# super.net
KiCad netlist of a schematic drawn in Altium Designer
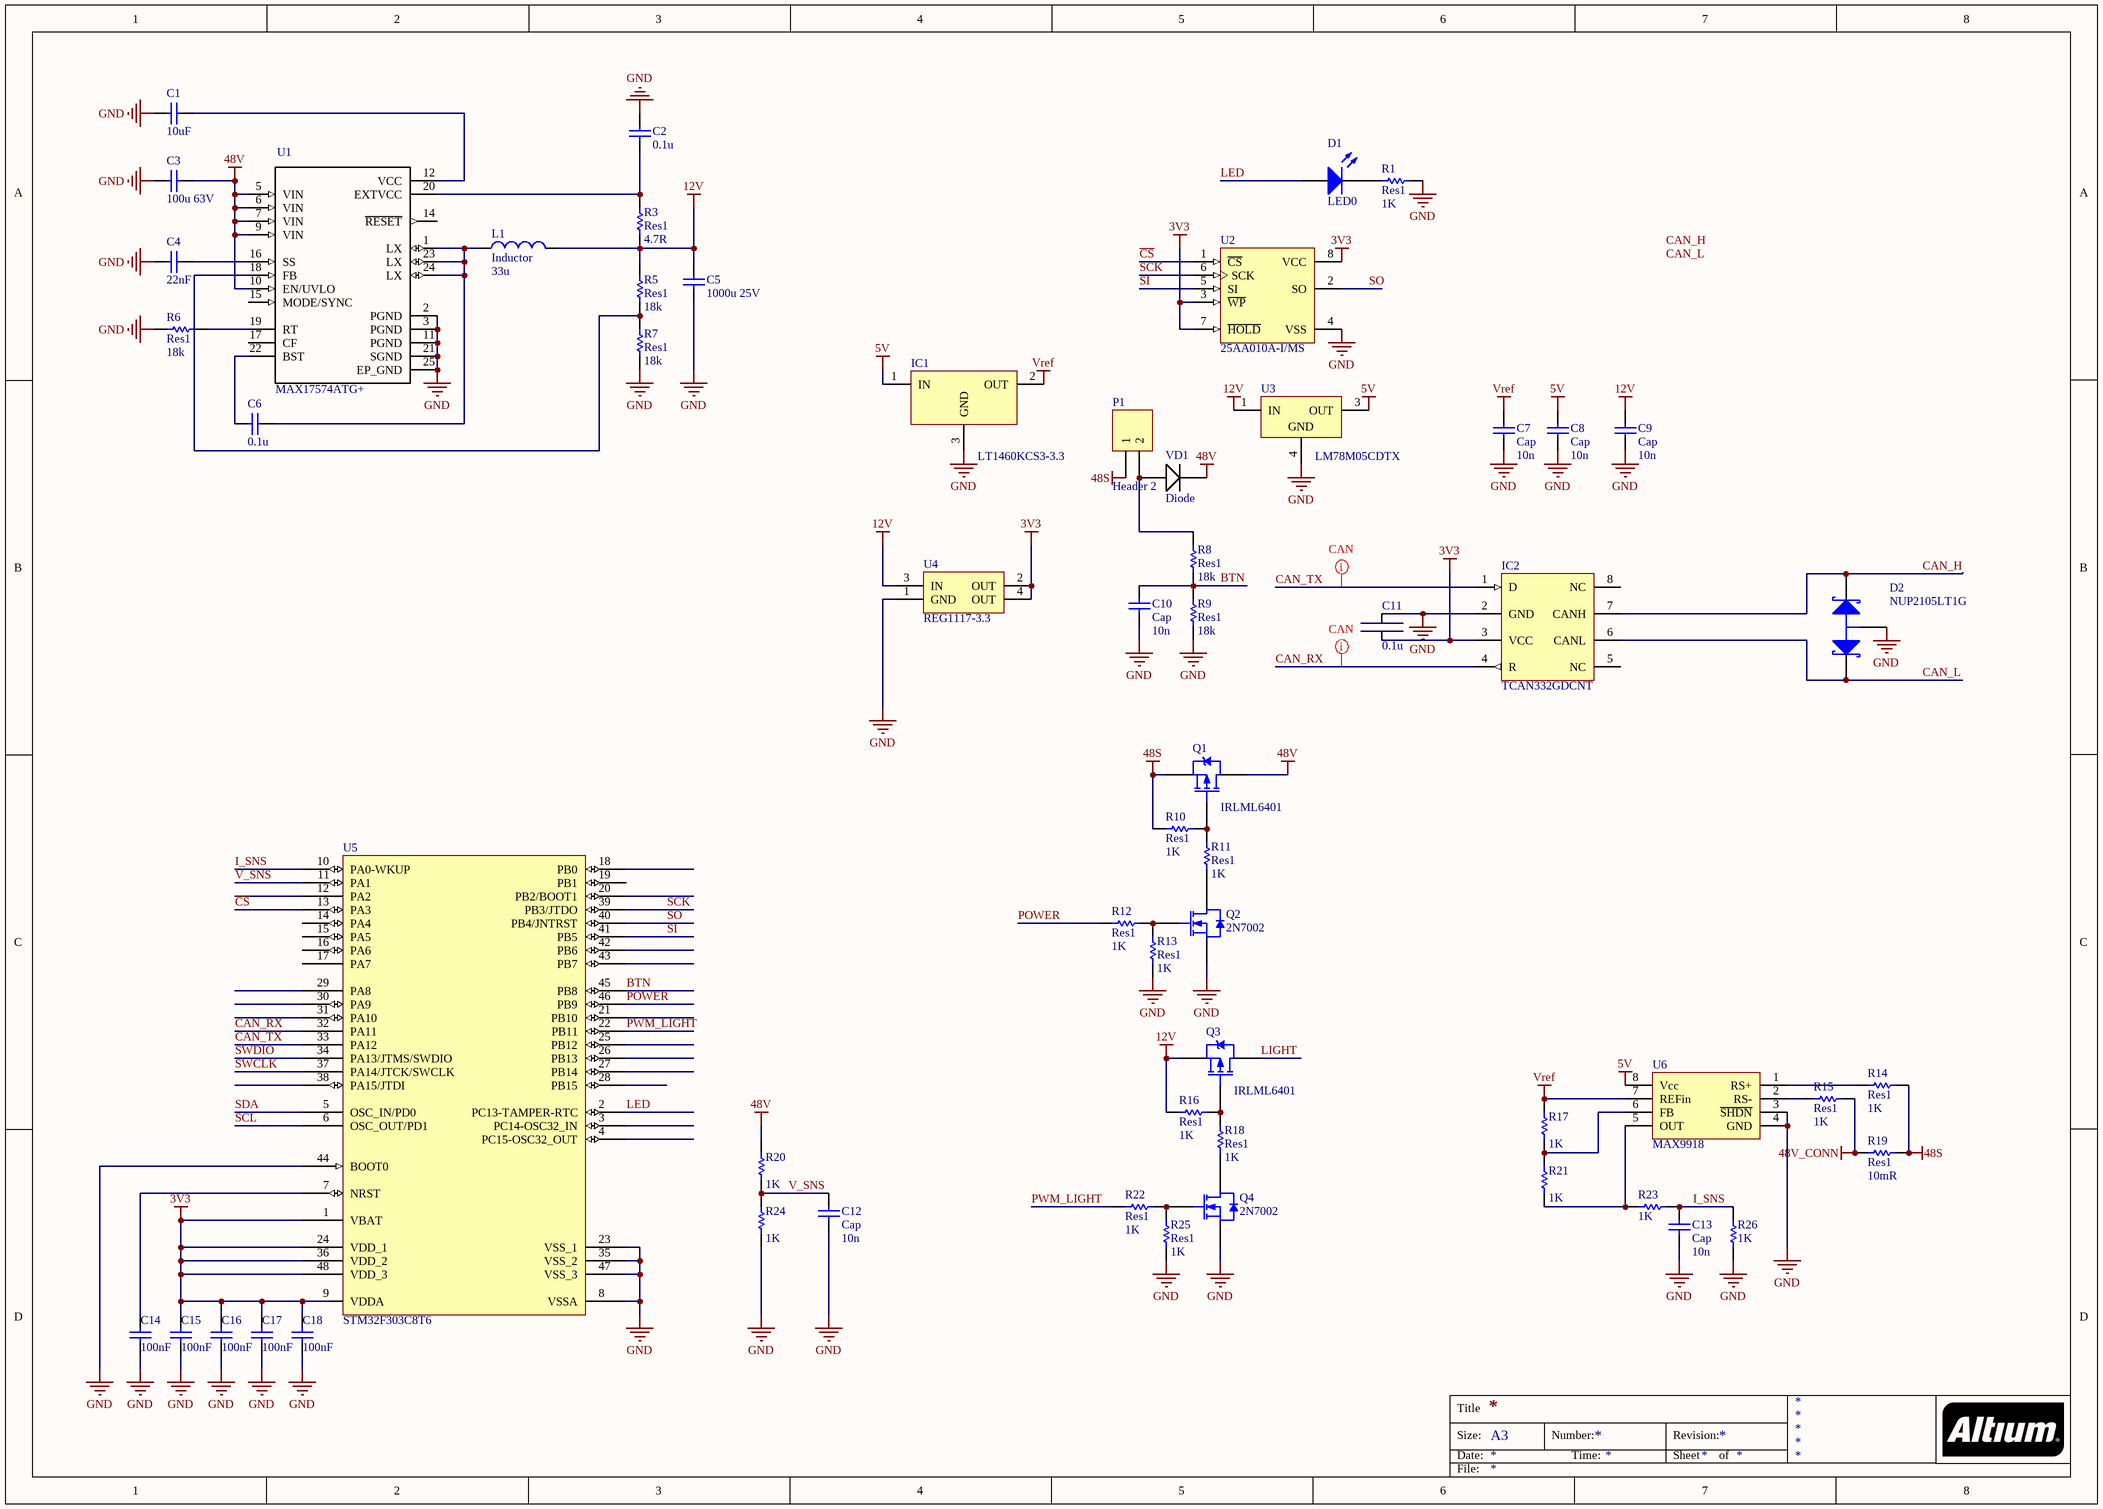
[diagram p0: super.SchDoc]

(export (version "E")
  (design (tool "Eeschema 10.0.6"))
  (components
    (comp (ref "C1")
      (value "10uF")
      (footprint "1206x")
      (description "Capacitor")
      (fields (field (name "PUBLISHER") "Altium Limited"))
      (libsource (lib "Miscellaneous Devices") (part "Cap"))
    )
    (comp (ref "C2")
      (value "0.1u")
      (footprint "0603x")
      (description "Capacitor")
      (fields (field (name "PUBLISHER") "Altium Limited"))
      (libsource (lib "Miscellaneous Devices") (part "Cap"))
    )
    (comp (ref "C3")
      (value "100u 63V")
      (footprint "CAP_ELEC_10mm")
      (description "Capacitor")
      (fields (field (name "PUBLISHER") "Altium Limited"))
      (libsource (lib "Miscellaneous Devices") (part "Cap"))
    )
    (comp (ref "C4")
      (value "22nF")
      (footprint "0603x")
      (description "Capacitor")
      (fields (field (name "PUBLISHER") "Altium Limited"))
      (libsource (lib "Miscellaneous Devices") (part "Cap"))
    )
    (comp (ref "C5")
      (value "1000u 25V")
      (footprint "CAP_ELEC_10mm")
      (description "Capacitor")
      (fields (field (name "PUBLISHER") "Altium Limited"))
      (libsource (lib "Miscellaneous Devices") (part "Cap"))
    )
    (comp (ref "C6")
      (value "0.1u")
      (footprint "0603x")
      (description "Capacitor")
      (fields (field (name "PUBLISHER") "Altium Limited"))
      (libsource (lib "Miscellaneous Devices") (part "Cap"))
    )
    (comp (ref "C7")
      (value "Cap")
      (footprint "0603x")
      (description "Capacitor")
      (fields (field (name "ALTIUM_VALUE") "10n") (field (name "PUBLISHER") "Altium Limited"))
      (libsource (lib "Miscellaneous Devices") (part "Cap"))
    )
    (comp (ref "C8")
      (value "Cap")
      (footprint "0603x")
      (description "Capacitor")
      (fields (field (name "ALTIUM_VALUE") "10n") (field (name "PUBLISHER") "Altium Limited"))
      (libsource (lib "Miscellaneous Devices") (part "Cap"))
    )
    (comp (ref "C9")
      (value "Cap")
      (footprint "0603x")
      (description "Capacitor")
      (fields (field (name "ALTIUM_VALUE") "10n") (field (name "PUBLISHER") "Altium Limited"))
      (libsource (lib "Miscellaneous Devices") (part "Cap"))
    )
    (comp (ref "C10")
      (value "Cap")
      (footprint "0603x")
      (description "Capacitor")
      (fields (field (name "ALTIUM_VALUE") "10n") (field (name "PUBLISHER") "Altium Limited"))
      (libsource (lib "Miscellaneous Devices") (part "Cap"))
    )
    (comp (ref "C11")
      (value "0.1u")
      (footprint "Condensator:CAPC1608X08N(0603)")
      (libsource (lib "Condensator") (part "Ceramic Chip Capacitor"))
    )
    (comp (ref "C12")
      (value "Cap")
      (footprint "0603x")
      (description "Capacitor")
      (fields (field (name "ALTIUM_VALUE") "10n") (field (name "PUBLISHER") "Altium Limited"))
      (libsource (lib "Miscellaneous Devices") (part "Cap"))
    )
    (comp (ref "C13")
      (value "Cap")
      (footprint "0603x")
      (description "Capacitor")
      (fields (field (name "ALTIUM_VALUE") "10n") (field (name "PUBLISHER") "Altium Limited"))
      (libsource (lib "Miscellaneous Devices") (part "Cap"))
    )
    (comp (ref "C14")
      (value "100nF")
      (footprint "0603x")
      (description "Capacitor")
      (fields (field (name "Comment") "Cap") (field (name "PUBLISHER") "Altium Limited"))
      (libsource (lib "Miscellaneous Devices") (part "Cap"))
    )
    (comp (ref "C15")
      (value "100nF")
      (footprint "0603x")
      (description "Capacitor")
      (fields (field (name "Comment") "Cap") (field (name "PUBLISHER") "Altium Limited"))
      (libsource (lib "Miscellaneous Devices") (part "Cap"))
    )
    (comp (ref "C16")
      (value "100nF")
      (footprint "0603x")
      (description "Capacitor")
      (fields (field (name "Comment") "Cap") (field (name "PUBLISHER") "Altium Limited"))
      (libsource (lib "Miscellaneous Devices") (part "Cap"))
    )
    (comp (ref "C17")
      (value "100nF")
      (footprint "0603x")
      (description "Capacitor")
      (fields (field (name "Comment") "Cap") (field (name "PUBLISHER") "Altium Limited"))
      (libsource (lib "Miscellaneous Devices") (part "Cap"))
    )
    (comp (ref "C18")
      (value "100nF")
      (footprint "0603x")
      (description "Capacitor")
      (fields (field (name "Comment") "Cap") (field (name "PUBLISHER") "Altium Limited"))
      (libsource (lib "Miscellaneous Devices") (part "Cap"))
    )
    (comp (ref "D1")
      (value "LED0")
      (footprint "HDR1X2")
      (description "Typical INFRARED GaAs LED")
      (fields (field (name "PUBLISHER") "Altium Limited"))
      (libsource (lib "Miscellaneous Devices") (part "LED0"))
    )
    (comp (ref "D2")
      (value "NUP2105LT1G")
      (footprint "SOT-23_M")
      (description "Schottky Barrier Double Diode")
      (libsource (lib "Philips Discrete Diode - Schottky") (part "BAT54A"))
    )
    (comp (ref "IC1")
      (value "LT1460KCS3-3.3")
      (footprint "SOT23_N")
      (libsource (lib "CustomLib") (part "PreciseRef"))
    )
    (comp (ref "IC2")
      (value "TCAN332GDCNT")
      (footprint "SOT23-8_L")
      (libsource (lib "CustomLib") (part "TCAN332GDCNT"))
    )
    (comp (ref "L1")
      (value "Inductor")
      (footprint "DR74")
      (fields (field (name "ALTIUM_VALUE") "33u") (field (name "PUBLISHER") "Altium Limited"))
      (libsource (lib "Miscellaneous Devices") (part "Inductor"))
    )
    (comp (ref "P1")
      (value "Header 2")
      (footprint "HDR1X2")
      (description "Header, 2-Pin")
      (fields (field (name "PUBLISHER") "Altium Limited"))
      (libsource (lib "Miscellaneous Connectors") (part "Header 2"))
    )
    (comp (ref "Q1")
      (value "IRLML6401")
      (footprint "Micro3_N")
      (description "HEXFET Power MOSFET")
      (fields (field (name "PUBLISHER") "Altium Limited"))
      (libsource (lib "IR Discrete MOSFET - Power") (part "IRLML6401"))
    )
    (comp (ref "Q2")
      (value "2N7002")
      (footprint "SOT23_N")
      (description "N-channel Enhancement Mode Field-effect Transistor")
      (fields (field (name "PUBLISHER") "Altium Limited"))
      (libsource (lib "Philips Discrete MOSFET - Low Power") (part "2N7002"))
    )
    (comp (ref "Q3")
      (value "IRLML6401")
      (footprint "Micro3_N")
      (description "HEXFET Power MOSFET")
      (fields (field (name "PUBLISHER") "Altium Limited"))
      (libsource (lib "IR Discrete MOSFET - Power") (part "IRLML6401"))
    )
    (comp (ref "Q4")
      (value "2N7002")
      (footprint "SOT23_N")
      (description "N-channel Enhancement Mode Field-effect Transistor")
      (fields (field (name "PUBLISHER") "Altium Limited"))
      (libsource (lib "Philips Discrete MOSFET - Low Power") (part "2N7002"))
    )
    (comp (ref "R1")
      (value "Res1")
      (footprint "0603x")
      (description "Resistor")
      (fields (field (name "ALTIUM_VALUE") "1K") (field (name "PUBLISHER") "Altium Limited"))
      (libsource (lib "Miscellaneous Devices") (part "Res1"))
    )
    (comp (ref "R3")
      (value "Res1")
      (footprint "0603x")
      (description "Resistor")
      (fields (field (name "ALTIUM_VALUE") "4.7R") (field (name "PUBLISHER") "Altium Limited"))
      (libsource (lib "Miscellaneous Devices") (part "Res1"))
    )
    (comp (ref "R5")
      (value "Res1")
      (footprint "0603x")
      (description "Resistor")
      (fields (field (name "ALTIUM_VALUE") "18k") (field (name "PUBLISHER") "Altium Limited"))
      (libsource (lib "Miscellaneous Devices") (part "Res1"))
    )
    (comp (ref "R6")
      (value "Res1")
      (footprint "0603x")
      (description "Resistor")
      (fields (field (name "ALTIUM_VALUE") "18k") (field (name "PUBLISHER") "Altium Limited"))
      (libsource (lib "Miscellaneous Devices") (part "Res1"))
    )
    (comp (ref "R7")
      (value "Res1")
      (footprint "0603x")
      (description "Resistor")
      (fields (field (name "ALTIUM_VALUE") "18k") (field (name "PUBLISHER") "Altium Limited"))
      (libsource (lib "Miscellaneous Devices") (part "Res1"))
    )
    (comp (ref "R8")
      (value "Res1")
      (footprint "0603x")
      (description "Resistor")
      (fields (field (name "ALTIUM_VALUE") "18k") (field (name "PUBLISHER") "Altium Limited"))
      (libsource (lib "Miscellaneous Devices") (part "Res1"))
    )
    (comp (ref "R9")
      (value "Res1")
      (footprint "0603x")
      (description "Resistor")
      (fields (field (name "ALTIUM_VALUE") "18k") (field (name "PUBLISHER") "Altium Limited"))
      (libsource (lib "Miscellaneous Devices") (part "Res1"))
    )
    (comp (ref "R10")
      (value "Res1")
      (footprint "0603x")
      (description "Resistor")
      (fields (field (name "ALTIUM_VALUE") "1K") (field (name "PUBLISHER") "Altium Limited"))
      (libsource (lib "Miscellaneous Devices") (part "Res1"))
    )
    (comp (ref "R11")
      (value "Res1")
      (footprint "0603x")
      (description "Resistor")
      (fields (field (name "ALTIUM_VALUE") "1K") (field (name "PUBLISHER") "Altium Limited"))
      (libsource (lib "Miscellaneous Devices") (part "Res1"))
    )
    (comp (ref "R12")
      (value "Res1")
      (footprint "1206x")
      (description "Resistor")
      (fields (field (name "ALTIUM_VALUE") "1K") (field (name "PUBLISHER") "Altium Limited"))
      (libsource (lib "Miscellaneous Devices") (part "Res1"))
    )
    (comp (ref "R13")
      (value "Res1")
      (footprint "0603x")
      (description "Resistor")
      (fields (field (name "ALTIUM_VALUE") "1K") (field (name "PUBLISHER") "Altium Limited"))
      (libsource (lib "Miscellaneous Devices") (part "Res1"))
    )
    (comp (ref "R14")
      (value "Res1")
      (footprint "0603x")
      (description "Resistor")
      (fields (field (name "ALTIUM_VALUE") "1K") (field (name "PUBLISHER") "Altium Limited"))
      (libsource (lib "Miscellaneous Devices") (part "Res1"))
    )
    (comp (ref "R15")
      (value "Res1")
      (footprint "0603x")
      (description "Resistor")
      (fields (field (name "ALTIUM_VALUE") "1K") (field (name "PUBLISHER") "Altium Limited"))
      (libsource (lib "Miscellaneous Devices") (part "Res1"))
    )
    (comp (ref "R16")
      (value "Res1")
      (footprint "0603x")
      (description "Resistor")
      (fields (field (name "ALTIUM_VALUE") "1K") (field (name "PUBLISHER") "Altium Limited"))
      (libsource (lib "Miscellaneous Devices") (part "Res1"))
    )
    (comp (ref "R17")
      (value "1K")
      (footprint "0603x")
      (description "Resistor")
      (fields (field (name "Comment") "Res1") (field (name "PUBLISHER") "Altium Limited"))
      (libsource (lib "Miscellaneous Devices") (part "Res1"))
    )
    (comp (ref "R18")
      (value "Res1")
      (footprint "0603x")
      (description "Resistor")
      (fields (field (name "ALTIUM_VALUE") "1K") (field (name "PUBLISHER") "Altium Limited"))
      (libsource (lib "Miscellaneous Devices") (part "Res1"))
    )
    (comp (ref "R19")
      (value "Res1")
      (footprint "2512")
      (description "Resistor")
      (fields (field (name "ALTIUM_VALUE") "10mR") (field (name "PUBLISHER") "Altium Limited"))
      (libsource (lib "Miscellaneous Devices") (part "Res1"))
    )
    (comp (ref "R20")
      (value "1K")
      (footprint "0603x")
      (description "Resistor")
      (fields (field (name "Comment") "Res1") (field (name "PUBLISHER") "Altium Limited"))
      (libsource (lib "Miscellaneous Devices") (part "Res1"))
    )
    (comp (ref "R21")
      (value "1K")
      (footprint "0603x")
      (description "Resistor")
      (fields (field (name "Comment") "Res1") (field (name "PUBLISHER") "Altium Limited"))
      (libsource (lib "Miscellaneous Devices") (part "Res1"))
    )
    (comp (ref "R22")
      (value "Res1")
      (footprint "0603x")
      (description "Resistor")
      (fields (field (name "ALTIUM_VALUE") "1K") (field (name "PUBLISHER") "Altium Limited"))
      (libsource (lib "Miscellaneous Devices") (part "Res1"))
    )
    (comp (ref "R23")
      (value "1K")
      (footprint "1206x")
      (description "Resistor")
      (fields (field (name "Comment") "Res1") (field (name "PUBLISHER") "Altium Limited"))
      (libsource (lib "Miscellaneous Devices") (part "Res1"))
    )
    (comp (ref "R24")
      (value "1K")
      (footprint "0603x")
      (description "Resistor")
      (fields (field (name "Comment") "Res1") (field (name "PUBLISHER") "Altium Limited"))
      (libsource (lib "Miscellaneous Devices") (part "Res1"))
    )
    (comp (ref "R25")
      (value "Res1")
      (footprint "0603x")
      (description "Resistor")
      (fields (field (name "ALTIUM_VALUE") "1K") (field (name "PUBLISHER") "Altium Limited"))
      (libsource (lib "Miscellaneous Devices") (part "Res1"))
    )
    (comp (ref "R26")
      (value "1K")
      (footprint "0603x")
      (description "Resistor")
      (fields (field (name "Comment") "Res1") (field (name "PUBLISHER") "Altium Limited"))
      (libsource (lib "Miscellaneous Devices") (part "Res1"))
    )
    (comp (ref "U1")
      (value "MAX17574ATG+")
      (footprint "QFN50P500X400X80-25N")
      (description "IC REG BUCK ADJ 3A SYNC 24TQFN")
      (fields (field (name "DIGI-KEY_PART_NUMBER") "MAX17574ATG+-ND") (field (name "MF") "Maxim Integrated"))
      (libsource (lib "MAX17574ATG_") (part "MAX17574ATG+"))
    )
    (comp (ref "U2")
      (value "25AA010A-I/MS")
      (footprint "SO-8_N")
      (description "1K SPI Bus Serial EEPROM, 8-Pin MSOP, Industrial Temperature")
      (fields (field (name "PUBLISHER") "Altium Limited"))
      (libsource (lib "Microchip Memory SPI Serial EEPROM") (part "25AA010A-I/MS"))
    )
    (comp (ref "U3")
      (value "LM78M05CDTX")
      (footprint "TO-252AA_L")
      (description "3-Terminal Positive Voltage Regulators, 3-pin TO-252")
      (fields
        (field (name "MANUFACTURER") "National Semiconductor")
        (field (name "PUBLISHER") "Altium Limited")
      )
      (libsource (lib "NSC LDO") (part "LM78M05CDTX"))
    )
    (comp (ref "U4")
      (value "REG1117-3.3")
      (footprint "SOt-223_L")
      (description "800mA and 1A Low Dropout Positive Regulator 2.85V, 3.3V, 5V, and Adjustable")
      (fields (field (name "PUBLISHER") "Altium Limited"))
      (libsource (lib "BB Power Mgt Voltage Regulator") (part "REG1117-3.3"))
    )
    (comp (ref "U5")
      (value "STM32F303C8T6")
      (footprint "LQFP48_N")
      (description "STM32 ARM-based 32-bit MCU with 32 Kbytes Flash, 48-pin LQFP, Industrial Temperature")
      (fields (field (name "PUBLISHER") "Altium Limited"))
      (libsource (lib "ST Microcontroller 32-Bit STM32") (part "STM32F103C6T6"))
    )
    (comp (ref "U6") (value "MAX9918") (footprint "SO8_M") (libsource (lib "CustomLib") (part "MAX9918")))
    (comp (ref "VD1")
      (value "Diode")
      (footprint "SOD-80/MLL34")
      (description "Default Diode")
      (fields (field (name "PUBLISHER") "Altium Limited"))
      (libsource (lib "EDDLib") (part "Diode"))
    )
  )
  (nets
    (net (code "1") (name "/BTN") (class "Default")
      (node (ref "C10") (pin "1") (pinfunction "1_1") (pintype "passive"))
      (node (ref "R8") (pin "1") (pinfunction "1_1") (pintype "passive"))
      (node (ref "R9") (pin "2") (pinfunction "2_2") (pintype "passive"))
      (node (ref "U5") (pin "45") (pinfunction "PB8_45") (pintype "bidirectional"))
    )
    (net (code "2") (name "/CAN_H") (class "Default")
      (node (ref "D2") (pin "2") (pinfunction "K2_2") (pintype "passive"))
      (node (ref "IC2") (pin "7") (pinfunction "CANH_7") (pintype "passive"))
    )
    (net (code "3") (name "/CAN_L") (class "Default")
      (node (ref "D2") (pin "1") (pinfunction "K1_1") (pintype "passive"))
      (node (ref "IC2") (pin "6") (pinfunction "CANL_6") (pintype "passive"))
    )
    (net (code "4") (name "/CAN_RX") (class "Default")
      (node (ref "IC2") (pin "4") (pinfunction "R_4") (pintype "output"))
      (node (ref "U5") (pin "32") (pinfunction "PA11_32") (pintype "passive"))
    )
    (net (code "5") (name "/CAN_TX") (class "Default")
      (node (ref "IC2") (pin "1") (pinfunction "D_1") (pintype "input"))
      (node (ref "U5") (pin "33") (pinfunction "PA12_33") (pintype "passive"))
    )
    (net (code "6") (name "/I_SNS") (class "Default")
      (node (ref "C13") (pin "1") (pinfunction "1_1") (pintype "passive"))
      (node (ref "R23") (pin "2") (pinfunction "2_2") (pintype "passive"))
      (node (ref "R26") (pin "2") (pinfunction "2_2") (pintype "passive"))
      (node (ref "U5") (pin "10") (pinfunction "PA0-WKUP_10") (pintype "bidirectional"))
    )
    (net (code "7") (name "/LED") (class "Default")
      (node (ref "D1") (pin "1") (pinfunction "A_1") (pintype "passive"))
      (node (ref "U5") (pin "2") (pinfunction "PC13-TAMPER-RTC_2") (pintype "bidirectional"))
    )
    (net (code "8") (name "/LIGHT") (class "Default")
      (node (ref "Q3") (pin "3") (pinfunction "D_3") (pintype "passive"))
    )
    (net (code "9") (name "/POWER") (class "Default")
      (node (ref "R12") (pin "1") (pinfunction "1_1") (pintype "passive"))
      (node (ref "U5") (pin "46") (pinfunction "PB9_46") (pintype "bidirectional"))
    )
    (net (code "10") (name "/PWM_LIGHT") (class "Default")
      (node (ref "R22") (pin "1") (pinfunction "1_1") (pintype "passive"))
      (node (ref "U5") (pin "22") (pinfunction "PB11_22") (pintype "bidirectional"))
    )
    (net (code "11") (name "/SCK") (class "Default")
      (node (ref "U2") (pin "6") (pinfunction "SCK_6") (pintype "input"))
      (node (ref "U5") (pin "39") (pinfunction "PB3/JTDO_39") (pintype "bidirectional"))
    )
    (net (code "12") (name "/SCL") (class "Default")
      (node (ref "U5") (pin "6") (pinfunction "OSC_OUT/PD1_6") (pintype "passive"))
    )
    (net (code "13") (name "/SDA") (class "Default")
      (node (ref "U5") (pin "5") (pinfunction "OSC_IN/PD0_5") (pintype "passive"))
    )
    (net (code "14") (name "/SI") (class "Default")
      (node (ref "U2") (pin "5") (pinfunction "SI_5") (pintype "input"))
      (node (ref "U5") (pin "41") (pinfunction "PB5_41") (pintype "bidirectional"))
    )
    (net (code "15") (name "/SO") (class "Default")
      (node (ref "U2") (pin "2") (pinfunction "SO_2") (pintype "tri_state"))
      (node (ref "U5") (pin "40") (pinfunction "PB4/JNTRST_40") (pintype "bidirectional"))
    )
    (net (code "16") (name "/SWCLK") (class "Default")
      (node (ref "U5") (pin "37") (pinfunction "PA14/JTCK/SWCLK_37") (pintype "passive"))
    )
    (net (code "17") (name "/SWDIO") (class "Default")
      (node (ref "U5") (pin "34") (pinfunction "PA13/JTMS/SWDIO_34") (pintype "passive"))
    )
    (net (code "18") (name "/V_SNS") (class "Default")
      (node (ref "C12") (pin "1") (pinfunction "1_1") (pintype "passive"))
      (node (ref "R20") (pin "2") (pinfunction "2_2") (pintype "passive"))
      (node (ref "R24") (pin "1") (pinfunction "1_1") (pintype "passive"))
      (node (ref "U5") (pin "11") (pinfunction "PA1_11") (pintype "bidirectional"))
    )
    (net (code "19") (name "/~{CS}") (class "Default")
      (node (ref "U2") (pin "1") (pinfunction "~{CS}_1") (pintype "input"))
      (node (ref "U5") (pin "13") (pinfunction "PA3_13") (pintype "bidirectional"))
    )
    (net (code "20") (name "3V3") (class "Default")
      (node (ref "C11") (pin "2") (pintype "passive"))
      (node (ref "C15") (pin "2") (pinfunction "2_2") (pintype "passive"))
      (node (ref "C16") (pin "2") (pinfunction "2_2") (pintype "passive"))
      (node (ref "C17") (pin "2") (pinfunction "2_2") (pintype "passive"))
      (node (ref "C18") (pin "2") (pinfunction "2_2") (pintype "passive"))
      (node (ref "IC2") (pin "3") (pinfunction "VCC_3") (pintype "passive"))
      (node (ref "U2") (pin "3") (pinfunction "~{WP}_3") (pintype "input"))
      (node (ref "U2") (pin "7") (pinfunction "~{HOLD}_7") (pintype "input"))
      (node (ref "U2") (pin "8") (pinfunction "VCC_8") (pintype "power_in"))
      (node (ref "U4") (pin "2") (pinfunction "OUT_2") (pintype "power_in"))
      (node (ref "U4") (pin "4") (pinfunction "OUT_4") (pintype "power_in"))
      (node (ref "U5") (pin "1") (pinfunction "VBAT_1") (pintype "power_in"))
      (node (ref "U5") (pin "24") (pinfunction "VDD_1_24") (pintype "power_in"))
      (node (ref "U5") (pin "36") (pinfunction "VDD_2_36") (pintype "power_in"))
      (node (ref "U5") (pin "48") (pinfunction "VDD_3_48") (pintype "power_in"))
      (node (ref "U5") (pin "9") (pinfunction "VDDA_9") (pintype "power_in"))
    )
    (net (code "21") (name "5V") (class "Default")
      (node (ref "C8") (pin "1") (pinfunction "1_1") (pintype "passive"))
      (node (ref "IC1") (pin "1") (pinfunction "IN_1") (pintype "passive"))
      (node (ref "U3") (pin "3") (pinfunction "OUT_3") (pintype "power_in"))
      (node (ref "U6") (pin "8") (pinfunction "Vcc_8") (pintype "passive"))
    )
    (net (code "22") (name "12V") (class "Default")
      (node (ref "C5") (pin "1") (pinfunction "1_1") (pintype "passive"))
      (node (ref "C9") (pin "1") (pinfunction "1_1") (pintype "passive"))
      (node (ref "L1") (pin "2") (pinfunction "2_2") (pintype "passive"))
      (node (ref "Q3") (pin "2") (pinfunction "S_2") (pintype "passive"))
      (node (ref "R16") (pin "1") (pinfunction "1_1") (pintype "passive"))
      (node (ref "R3") (pin "2") (pinfunction "2_2") (pintype "passive"))
      (node (ref "R5") (pin "2") (pinfunction "2_2") (pintype "passive"))
      (node (ref "U3") (pin "1") (pinfunction "IN_1") (pintype "power_in"))
      (node (ref "U4") (pin "3") (pinfunction "IN_3") (pintype "power_in"))
    )
    (net (code "23") (name "48S") (class "Default")
      (node (ref "P1") (pin "1") (pinfunction "1_1") (pintype "passive"))
      (node (ref "Q1") (pin "2") (pinfunction "S_2") (pintype "passive"))
      (node (ref "R10") (pin "1") (pinfunction "1_1") (pintype "passive"))
      (node (ref "R14") (pin "2") (pinfunction "2_2") (pintype "passive"))
      (node (ref "R19") (pin "2") (pinfunction "2_2") (pintype "passive"))
    )
    (net (code "24") (name "48V") (class "Default")
      (node (ref "C3") (pin "1") (pinfunction "1_1") (pintype "passive"))
      (node (ref "Q1") (pin "3") (pinfunction "D_3") (pintype "passive"))
      (node (ref "R20") (pin "1") (pinfunction "1_1") (pintype "passive"))
      (node (ref "U1") (pin "10") (pinfunction "EN/UVLO_10") (pintype "input"))
      (node (ref "U1") (pin "5") (pinfunction "VIN_5") (pintype "input"))
      (node (ref "U1") (pin "6") (pinfunction "VIN_6") (pintype "input"))
      (node (ref "U1") (pin "7") (pinfunction "VIN_7") (pintype "input"))
      (node (ref "U1") (pin "9") (pinfunction "VIN_9") (pintype "input"))
      (node (ref "VD1") (pin "2") (pinfunction "K_2") (pintype "passive"))
    )
    (net (code "25") (name "48V_CONN") (class "Default")
      (node (ref "R15") (pin "2") (pinfunction "2_2") (pintype "passive"))
      (node (ref "R19") (pin "1") (pinfunction "1_1") (pintype "passive"))
    )
    (net (code "26") (name "GND") (class "Default")
      (node (ref "C1") (pin "2") (pinfunction "2_2") (pintype "passive"))
      (node (ref "C10") (pin "2") (pinfunction "2_2") (pintype "passive"))
      (node (ref "C11") (pin "1") (pintype "passive"))
      (node (ref "C12") (pin "2") (pinfunction "2_2") (pintype "passive"))
      (node (ref "C13") (pin "2") (pinfunction "2_2") (pintype "passive"))
      (node (ref "C14") (pin "1") (pinfunction "1_1") (pintype "passive"))
      (node (ref "C15") (pin "1") (pinfunction "1_1") (pintype "passive"))
      (node (ref "C16") (pin "1") (pinfunction "1_1") (pintype "passive"))
      (node (ref "C17") (pin "1") (pinfunction "1_1") (pintype "passive"))
      (node (ref "C18") (pin "1") (pinfunction "1_1") (pintype "passive"))
      (node (ref "C2") (pin "2") (pinfunction "2_2") (pintype "passive"))
      (node (ref "C3") (pin "2") (pinfunction "2_2") (pintype "passive"))
      (node (ref "C4") (pin "1") (pinfunction "1_1") (pintype "passive"))
      (node (ref "C5") (pin "2") (pinfunction "2_2") (pintype "passive"))
      (node (ref "C7") (pin "2") (pinfunction "2_2") (pintype "passive"))
      (node (ref "C8") (pin "2") (pinfunction "2_2") (pintype "passive"))
      (node (ref "C9") (pin "2") (pinfunction "2_2") (pintype "passive"))
      (node (ref "D2") (pin "3") (pinfunction "A_3") (pintype "passive"))
      (node (ref "IC1") (pin "3") (pinfunction "GND_3") (pintype "passive"))
      (node (ref "IC2") (pin "2") (pinfunction "GND_2") (pintype "power_in"))
      (node (ref "Q2") (pin "2") (pinfunction "S_2") (pintype "passive"))
      (node (ref "Q4") (pin "2") (pinfunction "S_2") (pintype "passive"))
      (node (ref "R1") (pin "2") (pinfunction "2_2") (pintype "passive"))
      (node (ref "R13") (pin "1") (pinfunction "1_1") (pintype "passive"))
      (node (ref "R24") (pin "2") (pinfunction "2_2") (pintype "passive"))
      (node (ref "R25") (pin "1") (pinfunction "1_1") (pintype "passive"))
      (node (ref "R26") (pin "1") (pinfunction "1_1") (pintype "passive"))
      (node (ref "R6") (pin "2") (pinfunction "2_2") (pintype "passive"))
      (node (ref "R7") (pin "1") (pinfunction "1_1") (pintype "passive"))
      (node (ref "R9") (pin "1") (pinfunction "1_1") (pintype "passive"))
      (node (ref "U1") (pin "11") (pinfunction "PGND_11") (pintype "power_in"))
      (node (ref "U1") (pin "2") (pinfunction "PGND_2") (pintype "power_in"))
      (node (ref "U1") (pin "21") (pinfunction "SGND_21") (pintype "power_in"))
      (node (ref "U1") (pin "25") (pinfunction "EP_GND_25") (pintype "power_in"))
      (node (ref "U1") (pin "3") (pinfunction "PGND_3") (pintype "power_in"))
      (node (ref "U2") (pin "4") (pinfunction "VSS_4") (pintype "power_in"))
      (node (ref "U3") (pin "4") (pinfunction "GND_4") (pintype "power_in"))
      (node (ref "U4") (pin "1") (pinfunction "GND_1") (pintype "power_in"))
      (node (ref "U5") (pin "23") (pinfunction "VSS_1_23") (pintype "power_in"))
      (node (ref "U5") (pin "35") (pinfunction "VSS_2_35") (pintype "power_in"))
      (node (ref "U5") (pin "44") (pinfunction "BOOT0_44") (pintype "input"))
      (node (ref "U5") (pin "47") (pinfunction "VSS_3_47") (pintype "power_in"))
      (node (ref "U5") (pin "8") (pinfunction "VSSA_8") (pintype "power_in"))
      (node (ref "U6") (pin "3") (pinfunction "~{SHDN}_3") (pintype "passive"))
      (node (ref "U6") (pin "4") (pinfunction "GND_4") (pintype "passive"))
    )
    (net (code "27") (name "Net-(C6-Pad2)") (class "Default")
      (node (ref "C6") (pin "2") (pinfunction "2_2") (pintype "passive"))
      (node (ref "L1") (pin "1") (pinfunction "1_1") (pintype "passive"))
      (node (ref "U1") (pin "1") (pinfunction "LX_1") (pintype "bidirectional"))
      (node (ref "U1") (pin "23") (pinfunction "LX_23") (pintype "bidirectional"))
      (node (ref "U1") (pin "24") (pinfunction "LX_24") (pintype "bidirectional"))
    )
    (net (code "28") (name "Net-(D1-K)") (class "Default")
      (node (ref "D1") (pin "2") (pinfunction "K_2") (pintype "passive"))
      (node (ref "R1") (pin "1") (pinfunction "1_1") (pintype "passive"))
    )
    (net (code "29") (name "Net-(Q1-G)") (class "Default")
      (node (ref "Q1") (pin "1") (pinfunction "G_1") (pintype "passive"))
      (node (ref "R10") (pin "2") (pinfunction "2_2") (pintype "passive"))
      (node (ref "R11") (pin "1") (pinfunction "1_1") (pintype "passive"))
    )
    (net (code "30") (name "Net-(Q2-D)") (class "Default")
      (node (ref "Q2") (pin "3") (pinfunction "D_3") (pintype "passive"))
      (node (ref "R11") (pin "2") (pinfunction "2_2") (pintype "passive"))
    )
    (net (code "31") (name "Net-(Q2-G)") (class "Default")
      (node (ref "Q2") (pin "1") (pinfunction "G_1") (pintype "passive"))
      (node (ref "R12") (pin "2") (pinfunction "2_2") (pintype "passive"))
      (node (ref "R13") (pin "2") (pinfunction "2_2") (pintype "passive"))
    )
    (net (code "32") (name "Net-(Q3-G)") (class "Default")
      (node (ref "Q3") (pin "1") (pinfunction "G_1") (pintype "passive"))
      (node (ref "R16") (pin "2") (pinfunction "2_2") (pintype "passive"))
      (node (ref "R18") (pin "1") (pinfunction "1_1") (pintype "passive"))
    )
    (net (code "33") (name "Net-(Q4-D)") (class "Default")
      (node (ref "Q4") (pin "3") (pinfunction "D_3") (pintype "passive"))
      (node (ref "R18") (pin "2") (pinfunction "2_2") (pintype "passive"))
    )
    (net (code "34") (name "Net-(Q4-G)") (class "Default")
      (node (ref "Q4") (pin "1") (pinfunction "G_1") (pintype "passive"))
      (node (ref "R22") (pin "2") (pinfunction "2_2") (pintype "passive"))
      (node (ref "R25") (pin "2") (pinfunction "2_2") (pintype "passive"))
    )
    (net (code "35") (name "Net-(U1-BST)") (class "Default")
      (node (ref "C6") (pin "1") (pinfunction "1_1") (pintype "passive"))
      (node (ref "U1") (pin "22") (pinfunction "BST_22") (pintype "passive"))
    )
    (net (code "36") (name "Net-(U1-EXTVCC)") (class "Default")
      (node (ref "C2") (pin "1") (pinfunction "1_1") (pintype "passive"))
      (node (ref "R3") (pin "1") (pinfunction "1_1") (pintype "passive"))
      (node (ref "U1") (pin "20") (pinfunction "EXTVCC_20") (pintype "power_in"))
    )
    (net (code "37") (name "Net-(U1-FB)") (class "Default")
      (node (ref "R5") (pin "1") (pinfunction "1_1") (pintype "passive"))
      (node (ref "R7") (pin "2") (pinfunction "2_2") (pintype "passive"))
      (node (ref "U1") (pin "18") (pinfunction "FB_18") (pintype "input"))
    )
    (net (code "38") (name "Net-(U1-RT)") (class "Default")
      (node (ref "R6") (pin "1") (pinfunction "1_1") (pintype "passive"))
      (node (ref "U1") (pin "19") (pinfunction "RT_19") (pintype "passive"))
    )
    (net (code "39") (name "Net-(U1-SS)") (class "Default")
      (node (ref "C4") (pin "2") (pinfunction "2_2") (pintype "passive"))
      (node (ref "U1") (pin "16") (pinfunction "SS_16") (pintype "input"))
    )
    (net (code "40") (name "Net-(U1-VCC)") (class "Default")
      (node (ref "C1") (pin "1") (pinfunction "1_1") (pintype "passive"))
      (node (ref "U1") (pin "12") (pinfunction "VCC_12") (pintype "power_in"))
    )
    (net (code "41") (name "Net-(U5-NRST)") (class "Default")
      (node (ref "C14") (pin "2") (pinfunction "2_2") (pintype "passive"))
      (node (ref "U5") (pin "7") (pinfunction "NRST_7") (pintype "bidirectional"))
    )
    (net (code "42") (name "Net-(U6-FB)") (class "Default")
      (node (ref "R17") (pin "2") (pinfunction "2_2") (pintype "passive"))
      (node (ref "R21") (pin "1") (pinfunction "1_1") (pintype "passive"))
      (node (ref "U6") (pin "6") (pinfunction "FB_6") (pintype "passive"))
    )
    (net (code "43") (name "Net-(U6-OUT)") (class "Default")
      (node (ref "R21") (pin "2") (pinfunction "2_2") (pintype "passive"))
      (node (ref "R23") (pin "1") (pinfunction "1_1") (pintype "passive"))
      (node (ref "U6") (pin "5") (pinfunction "OUT_5") (pintype "passive"))
    )
    (net (code "44") (name "Net-(U6-RS+)") (class "Default")
      (node (ref "R14") (pin "1") (pinfunction "1_1") (pintype "passive"))
      (node (ref "U6") (pin "1") (pinfunction "RS+_1") (pintype "passive"))
    )
    (net (code "45") (name "Net-(U6-RS-)") (class "Default")
      (node (ref "R15") (pin "1") (pinfunction "1_1") (pintype "passive"))
      (node (ref "U6") (pin "2") (pinfunction "RS-_2") (pintype "passive"))
    )
    (net (code "46") (name "Net-(VD1-A)") (class "Default")
      (node (ref "P1") (pin "2") (pinfunction "2_2") (pintype "passive"))
      (node (ref "R8") (pin "2") (pinfunction "2_2") (pintype "passive"))
      (node (ref "VD1") (pin "1") (pinfunction "A_1") (pintype "passive"))
    )
    (net (code "47") (name "Vref") (class "Default")
      (node (ref "C7") (pin "1") (pinfunction "1_1") (pintype "passive"))
      (node (ref "IC1") (pin "2") (pinfunction "OUT_2") (pintype "passive"))
      (node (ref "R17") (pin "1") (pinfunction "1_1") (pintype "passive"))
      (node (ref "U6") (pin "7") (pinfunction "REFin_7") (pintype "passive"))
    )
    (net (code "48") (name "unconnected-(IC2-NC-Pad5)") (class "Default")
      (node (ref "IC2") (pin "5") (pinfunction "NC_5") (pintype "passive"))
    )
    (net (code "49") (name "unconnected-(IC2-NC-Pad8)") (class "Default")
      (node (ref "IC2") (pin "8") (pinfunction "NC_8") (pintype "passive"))
    )
    (net (code "50") (name "unconnected-(U1-CF-Pad17)") (class "Default")
      (node (ref "U1") (pin "17") (pinfunction "CF_17") (pintype "passive"))
    )
    (net (code "51") (name "unconnected-(U1-MODE{slash}SYNC-Pad15)") (class "Default")
      (node (ref "U1") (pin "15") (pinfunction "MODE/SYNC_15") (pintype "input"))
    )
    (net (code "52") (name "unconnected-(U1-~{RESET}-Pad14)") (class "Default")
      (node (ref "U1") (pin "14") (pinfunction "~{RESET}_14") (pintype "output"))
    )
    (net (code "53") (name "unconnected-(U5-PA2-Pad12)") (class "Default")
      (node (ref "U5") (pin "12") (pinfunction "PA2_12") (pintype "passive"))
    )
    (net (code "54") (name "unconnected-(U5-PA4-Pad14)") (class "Default")
      (node (ref "U5") (pin "14") (pinfunction "PA4_14") (pintype "bidirectional"))
    )
    (net (code "55") (name "unconnected-(U5-PA5-Pad15)") (class "Default")
      (node (ref "U5") (pin "15") (pinfunction "PA5_15") (pintype "bidirectional"))
    )
    (net (code "56") (name "unconnected-(U5-PA6-Pad16)") (class "Default")
      (node (ref "U5") (pin "16") (pinfunction "PA6_16") (pintype "bidirectional"))
    )
    (net (code "57") (name "unconnected-(U5-PA7-Pad17)") (class "Default")
      (node (ref "U5") (pin "17") (pinfunction "PA7_17") (pintype "passive"))
    )
    (net (code "58") (name "unconnected-(U5-PA8-Pad29)") (class "Default")
      (node (ref "U5") (pin "29") (pinfunction "PA8_29") (pintype "passive"))
    )
    (net (code "59") (name "unconnected-(U5-PA9-Pad30)") (class "Default")
      (node (ref "U5") (pin "30") (pinfunction "PA9_30") (pintype "bidirectional"))
    )
    (net (code "60") (name "unconnected-(U5-PA10-Pad31)") (class "Default")
      (node (ref "U5") (pin "31") (pinfunction "PA10_31") (pintype "bidirectional"))
    )
    (net (code "61") (name "unconnected-(U5-PA15{slash}JTDI-Pad38)") (class "Default")
      (node (ref "U5") (pin "38") (pinfunction "PA15/JTDI_38") (pintype "bidirectional"))
    )
    (net (code "62") (name "unconnected-(U5-PB0-Pad18)") (class "Default")
      (node (ref "U5") (pin "18") (pinfunction "PB0_18") (pintype "bidirectional"))
    )
    (net (code "63") (name "unconnected-(U5-PB1-Pad19)") (class "Default")
      (node (ref "U5") (pin "19") (pinfunction "PB1_19") (pintype "bidirectional"))
    )
    (net (code "64") (name "unconnected-(U5-PB2{slash}BOOT1-Pad20)") (class "Default")
      (node (ref "U5") (pin "20") (pinfunction "PB2/BOOT1_20") (pintype "bidirectional"))
    )
    (net (code "65") (name "unconnected-(U5-PB6-Pad42)") (class "Default")
      (node (ref "U5") (pin "42") (pinfunction "PB6_42") (pintype "bidirectional"))
    )
    (net (code "66") (name "unconnected-(U5-PB7-Pad43)") (class "Default")
      (node (ref "U5") (pin "43") (pinfunction "PB7_43") (pintype "bidirectional"))
    )
    (net (code "67") (name "unconnected-(U5-PB10-Pad21)") (class "Default")
      (node (ref "U5") (pin "21") (pinfunction "PB10_21") (pintype "bidirectional"))
    )
    (net (code "68") (name "unconnected-(U5-PB12-Pad25)") (class "Default")
      (node (ref "U5") (pin "25") (pinfunction "PB12_25") (pintype "bidirectional"))
    )
    (net (code "69") (name "unconnected-(U5-PB13-Pad26)") (class "Default")
      (node (ref "U5") (pin "26") (pinfunction "PB13_26") (pintype "bidirectional"))
    )
    (net (code "70") (name "unconnected-(U5-PB14-Pad27)") (class "Default")
      (node (ref "U5") (pin "27") (pinfunction "PB14_27") (pintype "bidirectional"))
    )
    (net (code "71") (name "unconnected-(U5-PB15-Pad28)") (class "Default")
      (node (ref "U5") (pin "28") (pinfunction "PB15_28") (pintype "bidirectional"))
    )
    (net (code "72") (name "unconnected-(U5-PC14-OSC32_IN-Pad3)") (class "Default")
      (node (ref "U5") (pin "3") (pinfunction "PC14-OSC32_IN_3") (pintype "bidirectional"))
    )
    (net (code "73") (name "unconnected-(U5-PC15-OSC32_OUT-Pad4)") (class "Default")
      (node (ref "U5") (pin "4") (pinfunction "PC15-OSC32_OUT_4") (pintype "bidirectional"))
    )
  )
)
